# Sheet2.net
KiCad netlist of a schematic drawn in Altium Designer
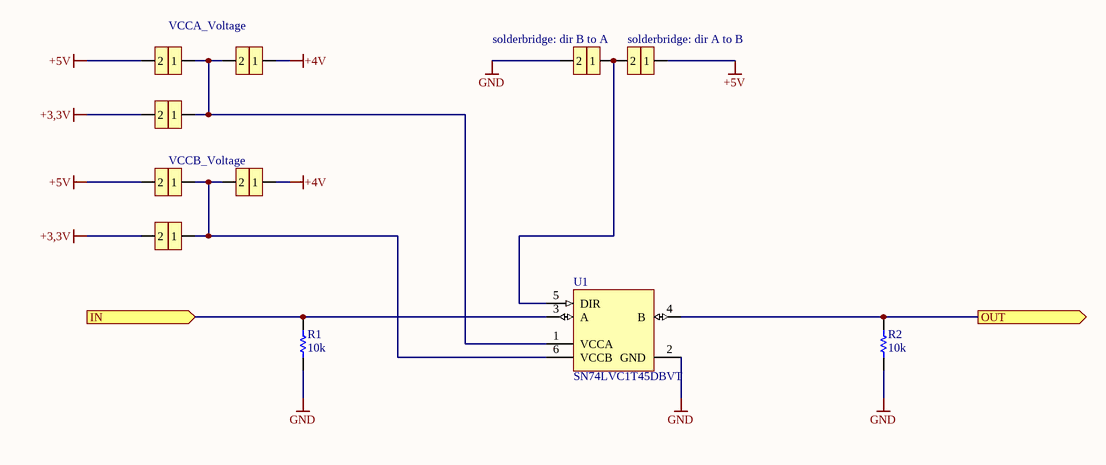
[diagram p0: Sheet2.SchDoc]

(export (version "E")
  (design (tool "Eeschema 10.0.6"))
  (components
    (comp (ref "J1")
      (value "normal solderbridge")
      (footprint "PCBComponent")
      (libsource (lib "Altium Vault EMBL 3") (part "CMP-001-0133-A.1"))
    )
    (comp (ref "J2")
      (value "normal solderbridge")
      (footprint "PCBComponent")
      (libsource (lib "Altium Vault EMBL 3") (part "CMP-001-0133-A.1"))
    )
    (comp (ref "J3")
      (value "normal solderbridge")
      (footprint "PCBComponent")
      (libsource (lib "Altium Vault EMBL 3") (part "CMP-001-0133-A.1"))
    )
    (comp (ref "J4")
      (value "normal solderbridge")
      (footprint "PCBComponent")
      (libsource (lib "Altium Vault EMBL 3") (part "CMP-001-0133-A.1"))
    )
    (comp (ref "J5")
      (value "normal solderbridge")
      (footprint "PCBComponent")
      (libsource (lib "Altium Vault EMBL 3") (part "CMP-001-0133-A.1"))
    )
    (comp (ref "J6")
      (value "normal solderbridge")
      (footprint "PCBComponent")
      (libsource (lib "Altium Vault EMBL 3") (part "CMP-001-0133-A.1"))
    )
    (comp (ref "J7")
      (value "normal solderbridge")
      (footprint "PCBComponent")
      (libsource (lib "Altium Vault EMBL 3") (part "CMP-001-0133-A.1"))
    )
    (comp (ref "J8")
      (value "normal solderbridge")
      (footprint "PCBComponent")
      (libsource (lib "Altium Vault EMBL 3") (part "CMP-001-0133-A.1"))
    )
    (comp (ref "R1")
      (value "10k")
      (footprint "YAGO-RC0805_M")
      (description "0805 Yageo Standard BlackBox Resistors")
      (fields (field (name "TOLERANCE") "±1%") (field (name "MANUFACTURER") "Yageo"))
      (libsource (lib "Altium Vault EMBL 3") (part "CMP-001-0027-2"))
    )
    (comp (ref "R2")
      (value "10k")
      (footprint "YAGO-RC0805_M")
      (description "0805 Yageo Standard BlackBox Resistors")
      (fields (field (name "TOLERANCE") "±1%") (field (name "MANUFACTURER") "Yageo"))
      (libsource (lib "Altium Vault EMBL") (part "CMP-001-0027-2"))
    )
    (comp (ref "U1")
      (value "SN74LVC1T45DBVT")
      (footprint "DBV0006A_M")
      (fields
        (field (name "MANUFACTURER") "Texas Instruments")
        (field (name "GENERIC PART NUMBER") "SN74LVC1T45")
      )
      (libsource (lib "Altium Vault EMBL 3") (part "CMP-00491-1"))
    )
  )
  (nets
    (net (code "1") (name "+3,3V") (class "Default")
      (node (ref "J3") (pin "2") (pinfunction "2_2") (pintype "passive"))
      (node (ref "J6") (pin "2") (pinfunction "2_2") (pintype "passive"))
    )
    (net (code "2") (name "+4V") (class "Default")
      (node (ref "J2") (pin "1") (pinfunction "1_1") (pintype "passive"))
      (node (ref "J5") (pin "1") (pinfunction "1_1") (pintype "passive"))
    )
    (net (code "3") (name "+5V") (class "Default")
      (node (ref "J1") (pin "2") (pinfunction "2_2") (pintype "passive"))
      (node (ref "J4") (pin "2") (pinfunction "2_2") (pintype "passive"))
      (node (ref "J8") (pin "1") (pinfunction "1_1") (pintype "passive"))
    )
    (net (code "4") (name "/IN") (class "Default")
      (node (ref "R1") (pin "2") (pinfunction "2_2") (pintype "passive"))
      (node (ref "U1") (pin "3") (pinfunction "A_3") (pintype "bidirectional"))
    )
    (net (code "5") (name "/OUT") (class "Default")
      (node (ref "R2") (pin "2") (pinfunction "2_2") (pintype "passive"))
      (node (ref "U1") (pin "4") (pinfunction "B_4") (pintype "bidirectional"))
    )
    (net (code "6") (name "GND") (class "Default")
      (node (ref "J7") (pin "2") (pinfunction "2_2") (pintype "passive"))
      (node (ref "R1") (pin "1") (pinfunction "1_1") (pintype "passive"))
      (node (ref "R2") (pin "1") (pinfunction "1_1") (pintype "passive"))
      (node (ref "U1") (pin "2") (pinfunction "GND_2") (pintype "power_in"))
    )
    (net (code "7") (name "Net-(U1-DIR)") (class "Default")
      (node (ref "J7") (pin "1") (pinfunction "1_1") (pintype "passive"))
      (node (ref "J8") (pin "2") (pinfunction "2_2") (pintype "passive"))
      (node (ref "U1") (pin "5") (pinfunction "DIR_5") (pintype "input"))
    )
    (net (code "8") (name "Net-(U1-VCCA)") (class "Default")
      (node (ref "J1") (pin "1") (pinfunction "1_1") (pintype "passive"))
      (node (ref "J2") (pin "2") (pinfunction "2_2") (pintype "passive"))
      (node (ref "J3") (pin "1") (pinfunction "1_1") (pintype "passive"))
      (node (ref "U1") (pin "1") (pinfunction "VCCA_1") (pintype "power_in"))
    )
    (net (code "9") (name "Net-(U1-VCCB)") (class "Default")
      (node (ref "J4") (pin "1") (pinfunction "1_1") (pintype "passive"))
      (node (ref "J5") (pin "2") (pinfunction "2_2") (pintype "passive"))
      (node (ref "J6") (pin "1") (pinfunction "1_1") (pintype "passive"))
      (node (ref "U1") (pin "6") (pinfunction "VCCB_6") (pintype "power_in"))
    )
  )
)
